# Ponte_H.net
KiCad netlist of a schematic drawn in Altium Designer
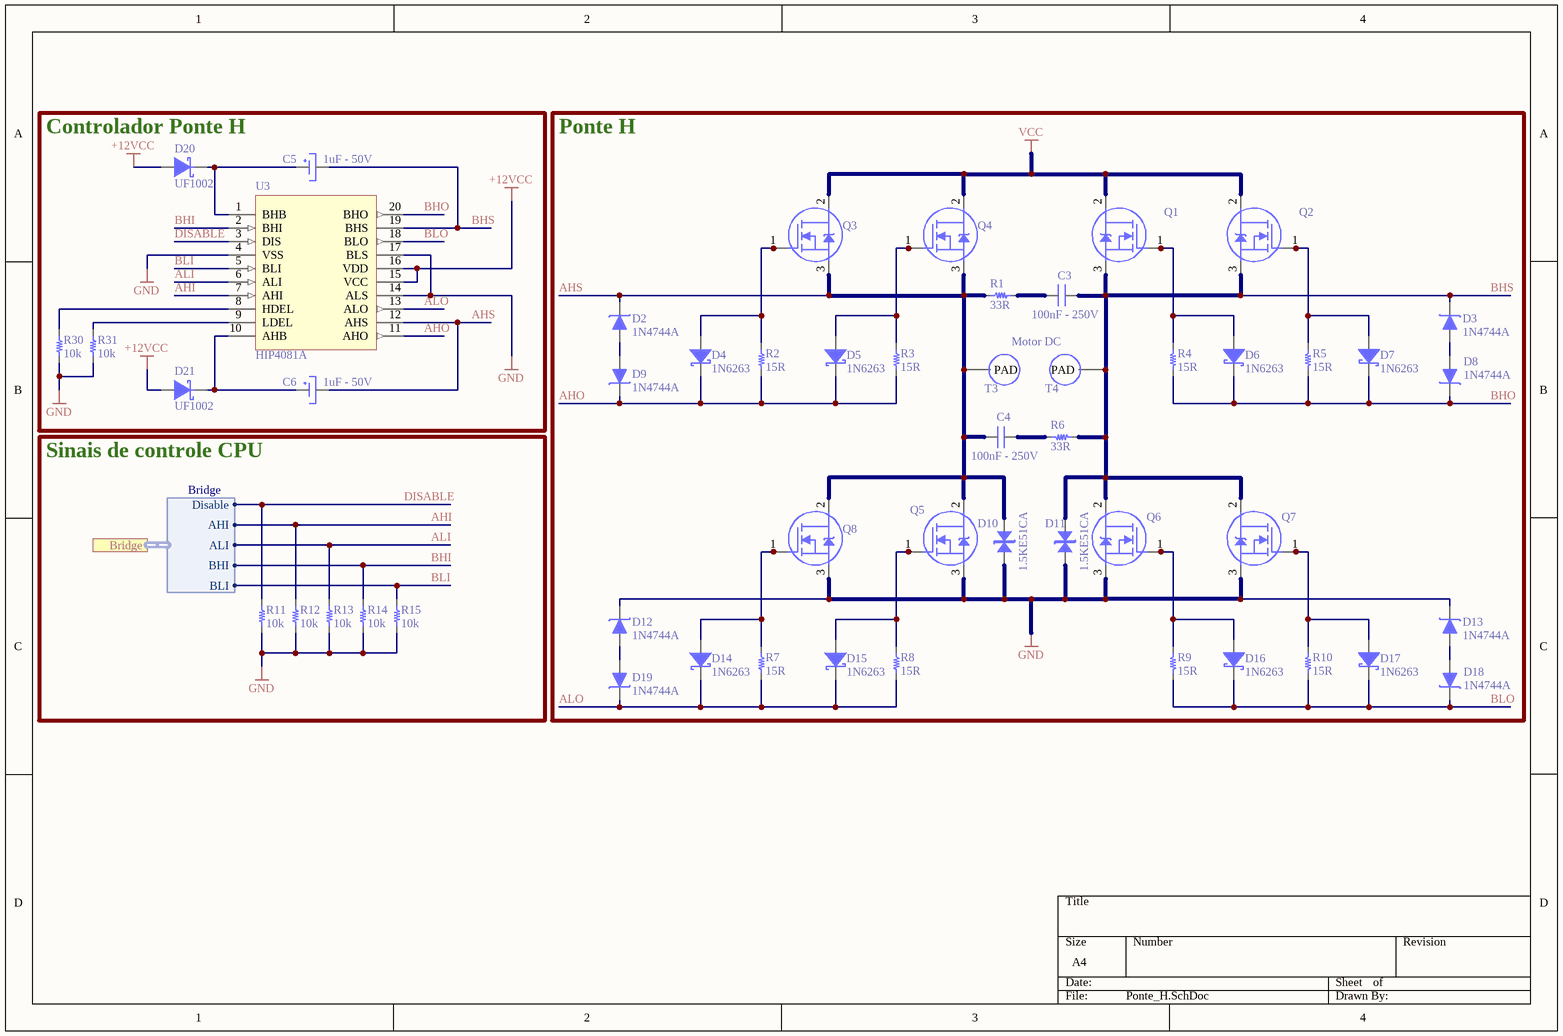
[diagram p0: Ponte_H.SchDoc]

(export (version "E")
  (design (tool "Eeschema 10.0.6"))
  (components
    (comp (ref "C3")
      (value "100nF - 250V")
      (footprint "Capacitor_PTH")
      (description "Capacitor_100nF Poliester")
      (libsource (lib "bike") (part "100nF - 250V"))
    )
    (comp (ref "C4")
      (value "100nF - 250V")
      (footprint "Capacitor_PTH")
      (description "Capacitor_100nF Poliester")
      (libsource (lib "bike") (part "100nF - 250V"))
    )
    (comp (ref "C5")
      (value "1uF - 50V")
      (footprint "CAPACITOR_SMD")
      (description "Capacitor_1uF_50V")
      (libsource (lib "bike") (part "1uF - 50V"))
    )
    (comp (ref "C6")
      (value "1uF - 50V")
      (footprint "CAPACITOR_SMD")
      (description "Capacitor_1uF_50V")
      (libsource (lib "bike") (part "1uF - 50V"))
    )
    (comp (ref "D2")
      (value "1N4744A")
      (footprint "Diode_PHT")
      (description "Diodo Zener 15V 200mA")
      (libsource (lib "bike") (part "1N4744A"))
    )
    (comp (ref "D3")
      (value "1N4744A")
      (footprint "Diode_PHT")
      (description "Diodo Zener 15V 200mA")
      (libsource (lib "bike") (part "1N4744A"))
    )
    (comp (ref "D4")
      (value "1N6263")
      (footprint "Diode_PHT")
      (description "Diodo Schottky 60V - 15mA")
      (libsource (lib "bike") (part "1N6263"))
    )
    (comp (ref "D5")
      (value "1N6263")
      (footprint "Diode_PHT")
      (description "Diodo Schottky 60V - 15mA")
      (libsource (lib "bike") (part "1N6263"))
    )
    (comp (ref "D6")
      (value "1N6263")
      (footprint "Diode_PHT")
      (description "Diodo Schottky 60V - 15mA")
      (libsource (lib "bike") (part "1N6263"))
    )
    (comp (ref "D7")
      (value "1N6263")
      (footprint "Diode_PHT")
      (description "Diodo Schottky 60V - 15mA")
      (libsource (lib "bike") (part "1N6263"))
    )
    (comp (ref "D8")
      (value "1N4744A")
      (footprint "Diode_PHT")
      (description "Diodo Zener 15V 200mA")
      (libsource (lib "bike") (part "1N4744A"))
    )
    (comp (ref "D9")
      (value "1N4744A")
      (footprint "Diode_PHT")
      (description "Diodo Zener 15V 200mA")
      (libsource (lib "bike") (part "1N4744A"))
    )
    (comp (ref "D10")
      (value "1.5KE51CA")
      (footprint "DO-201")
      (description "Transzorb")
      (libsource (lib "bike") (part "1.5KE51CA"))
    )
    (comp (ref "D11")
      (value "1.5KE51CA")
      (footprint "DO-201")
      (description "Transzorb")
      (libsource (lib "bike") (part "1.5KE51CA"))
    )
    (comp (ref "D12")
      (value "1N4744A")
      (footprint "Diode_PHT")
      (description "Diodo Zener 15V 200mA")
      (libsource (lib "bike") (part "1N4744A"))
    )
    (comp (ref "D13")
      (value "1N4744A")
      (footprint "Diode_PHT")
      (description "Diodo Zener 15V 200mA")
      (libsource (lib "bike") (part "1N4744A"))
    )
    (comp (ref "D14")
      (value "1N6263")
      (footprint "Diode_PHT")
      (description "Diodo Schottky 60V - 15mA")
      (libsource (lib "bike") (part "1N6263"))
    )
    (comp (ref "D15")
      (value "1N6263")
      (footprint "Diode_PHT")
      (description "Diodo Schottky 60V - 15mA")
      (libsource (lib "bike") (part "1N6263"))
    )
    (comp (ref "D16")
      (value "1N6263")
      (footprint "Diode_PHT")
      (description "Diodo Schottky 60V - 15mA")
      (libsource (lib "bike") (part "1N6263"))
    )
    (comp (ref "D17")
      (value "1N6263")
      (footprint "Diode_PHT")
      (description "Diodo Schottky 60V - 15mA")
      (libsource (lib "bike") (part "1N6263"))
    )
    (comp (ref "D18")
      (value "1N4744A")
      (footprint "Diode_PHT")
      (description "Diodo Zener 15V 200mA")
      (libsource (lib "bike") (part "1N4744A"))
    )
    (comp (ref "D19")
      (value "1N4744A")
      (footprint "Diode_PHT")
      (description "Diodo Zener 15V 200mA")
      (libsource (lib "bike") (part "1N4744A"))
    )
    (comp (ref "D20")
      (value "UF1002")
      (footprint "Diode_PHT")
      (description "UltraFast Diode 1.0A")
      (libsource (lib "bike") (part "UF1002"))
    )
    (comp (ref "D21")
      (value "UF1002")
      (footprint "Diode_PHT")
      (description "UltraFast Diode 1.0A")
      (libsource (lib "bike") (part "UF1002"))
    )
    (comp (ref "Q1")
      (value "IRF1405")
      (footprint "TO-220AB")
      (description "MOSFET transistor")
      (libsource (lib "bike") (part "IRF1405"))
    )
    (comp (ref "Q2")
      (value "IRF1405")
      (footprint "TO-220AB")
      (description "MOSFET transistor")
      (libsource (lib "bike") (part "IRF1405"))
    )
    (comp (ref "Q3")
      (value "IRF1405")
      (footprint "TO-220AB")
      (description "MOSFET transistor")
      (libsource (lib "") (part "IRF1405_1"))
    )
    (comp (ref "Q4")
      (value "IRF1405")
      (footprint "TO-220AB")
      (description "MOSFET transistor")
      (libsource (lib "") (part "IRF1405_1"))
    )
    (comp (ref "Q5")
      (value "IRF1405")
      (footprint "TO-220AB")
      (description "MOSFET transistor")
      (libsource (lib "") (part "IRF1405_1"))
    )
    (comp (ref "Q6")
      (value "IRF1405")
      (footprint "TO-220AB")
      (description "MOSFET transistor")
      (libsource (lib "bike") (part "IRF1405"))
    )
    (comp (ref "Q7")
      (value "IRF1405")
      (footprint "TO-220AB")
      (description "MOSFET transistor")
      (libsource (lib "bike") (part "IRF1405"))
    )
    (comp (ref "Q8")
      (value "IRF1405")
      (footprint "TO-220AB")
      (description "MOSFET transistor")
      (libsource (lib "") (part "IRF1405_1"))
    )
    (comp (ref "R1")
      (value "33R")
      (footprint "Resistor_PTH")
      (description "Resistor PHT")
      (libsource (lib "bike") (part "Resistor_33R"))
    )
    (comp (ref "R2")
      (value "15R")
      (footprint "R_0805")
      (description "Resistor padrão 0805")
      (libsource (lib "bike") (part "Resistor_15R"))
    )
    (comp (ref "R3")
      (value "15R")
      (footprint "R_0805")
      (description "Resistor padrão 0805")
      (libsource (lib "bike") (part "Resistor_15R"))
    )
    (comp (ref "R4")
      (value "15R")
      (footprint "R_0805")
      (description "Resistor padrão 0805")
      (libsource (lib "bike") (part "Resistor_15R"))
    )
    (comp (ref "R5")
      (value "15R")
      (footprint "R_0805")
      (description "Resistor padrão 0805")
      (libsource (lib "bike") (part "Resistor_15R"))
    )
    (comp (ref "R6")
      (value "33R")
      (footprint "Resistor_PTH")
      (description "Resistor PHT")
      (libsource (lib "bike") (part "Resistor_33R"))
    )
    (comp (ref "R7")
      (value "15R")
      (footprint "R_0805")
      (description "Resistor padrão 0805")
      (libsource (lib "bike") (part "Resistor_15R"))
    )
    (comp (ref "R8")
      (value "15R")
      (footprint "R_0805")
      (description "Resistor padrão 0805")
      (libsource (lib "bike") (part "Resistor_15R"))
    )
    (comp (ref "R9")
      (value "15R")
      (footprint "R_0805")
      (description "Resistor padrão 0805")
      (libsource (lib "bike") (part "Resistor_15R"))
    )
    (comp (ref "R10")
      (value "15R")
      (footprint "R_0805")
      (description "Resistor padrão 0805")
      (libsource (lib "bike") (part "Resistor_15R"))
    )
    (comp (ref "R11")
      (value "10k")
      (footprint "R_0805")
      (description "Resistor padrão 0805")
      (libsource (lib "bike") (part "Resistor_10K"))
    )
    (comp (ref "R12")
      (value "10k")
      (footprint "R_0805")
      (description "Resistor padrão 0805")
      (libsource (lib "bike") (part "Resistor_10K"))
    )
    (comp (ref "R13")
      (value "10k")
      (footprint "R_0805")
      (description "Resistor padrão 0805")
      (libsource (lib "bike") (part "Resistor_10K"))
    )
    (comp (ref "R14")
      (value "10k")
      (footprint "R_0805")
      (description "Resistor padrão 0805")
      (libsource (lib "bike") (part "Resistor_10K"))
    )
    (comp (ref "R15")
      (value "10k")
      (footprint "R_0805")
      (description "Resistor padrão 0805")
      (libsource (lib "bike") (part "Resistor_10K"))
    )
    (comp (ref "R30")
      (value "10k")
      (footprint "R_0805")
      (description "Resistor padrão 0805")
      (libsource (lib "bike") (part "Resistor_10K"))
    )
    (comp (ref "R31")
      (value "10k")
      (footprint "R_0805")
      (description "Resistor padrão 0805")
      (libsource (lib "bike") (part "Resistor_10K"))
    )
    (comp (ref "T3")
      (value "Power_Pad")
      (footprint "Power_Pad")
      (description "Terminal de alta potência para soldar os cabos de potência")
      (libsource (lib "bike") (part "Power_Pad"))
    )
    (comp (ref "T4")
      (value "Power_Pad")
      (footprint "Power_Pad")
      (description "Terminal de alta potência para soldar os cabos de potência")
      (libsource (lib "bike") (part "Power_Pad"))
    )
    (comp (ref "U3")
      (value "HIP4081A")
      (footprint "PDIP20")
      (description "High Frequency Full Bridge FET Driver")
      (libsource (lib "bike") (part "HIP4081A"))
    )
  )
  (nets
    (net (code "2") (name "+12VCC") (class "Default")
      (node (ref "D20") (pin "A") (pinfunction "Anodo_A") (pintype "passive"))
      (node (ref "D21") (pin "A") (pinfunction "Anodo_A") (pintype "passive"))
      (node (ref "U3") (pin "15") (pinfunction "VCC_15") (pintype "power_in"))
      (node (ref "U3") (pin "16") (pinfunction "VDD_16") (pintype "power_in"))
    )
    (net (code "3") (name "/AHI") (class "Default")
      (node (ref "R12") (pin "2") (pinfunction "2_2") (pintype "passive"))
      (node (ref "U3") (pin "7") (pinfunction "AHI_7") (pintype "input"))
    )
    (net (code "4") (name "/AHO") (class "Default")
      (node (ref "D4") (pin "K") (pinfunction "Catodo_K") (pintype "passive"))
      (node (ref "D5") (pin "K") (pinfunction "Catodo_K") (pintype "passive"))
      (node (ref "D9") (pin "K") (pinfunction "Catodo_K") (pintype "passive"))
      (node (ref "R2") (pin "1") (pinfunction "1_1") (pintype "passive"))
      (node (ref "R3") (pin "1") (pinfunction "1_1") (pintype "passive"))
      (node (ref "U3") (pin "11") (pinfunction "AHO_11") (pintype "output"))
    )
    (net (code "5") (name "/AHS") (class "Default")
      (node (ref "C4") (pin "1") (pinfunction "1_1") (pintype "passive"))
      (node (ref "C6") (pin "1") (pinfunction "1_1") (pintype "passive"))
      (node (ref "D10") (pin "K") (pinfunction "Catodo_K") (pintype "passive"))
      (node (ref "D2") (pin "K") (pinfunction "Catodo_K") (pintype "passive"))
      (node (ref "Q3") (pin "3") (pinfunction "Source_3") (pintype "power_in"))
      (node (ref "Q4") (pin "3") (pinfunction "Source_3") (pintype "power_in"))
      (node (ref "Q5") (pin "2") (pinfunction "Drain_2") (pintype "power_in"))
      (node (ref "Q8") (pin "2") (pinfunction "Drain_2") (pintype "power_in"))
      (node (ref "R1") (pin "1") (pinfunction "1_1") (pintype "passive"))
      (node (ref "T3") (pin "1") (pinfunction "PAD_1") (pintype "power_in"))
      (node (ref "U3") (pin "12") (pinfunction "AHS_12") (pintype "power_in"))
    )
    (net (code "6") (name "/ALI") (class "Default")
      (node (ref "R13") (pin "2") (pinfunction "2_2") (pintype "passive"))
      (node (ref "U3") (pin "6") (pinfunction "ALI_6") (pintype "input"))
    )
    (net (code "7") (name "/ALO") (class "Default")
      (node (ref "D14") (pin "K") (pinfunction "Catodo_K") (pintype "passive"))
      (node (ref "D15") (pin "K") (pinfunction "Catodo_K") (pintype "passive"))
      (node (ref "D19") (pin "K") (pinfunction "Catodo_K") (pintype "passive"))
      (node (ref "R7") (pin "1") (pinfunction "1_1") (pintype "passive"))
      (node (ref "R8") (pin "1") (pinfunction "1_1") (pintype "passive"))
      (node (ref "U3") (pin "13") (pinfunction "ALO_13") (pintype "output"))
    )
    (net (code "8") (name "/BHI") (class "Default")
      (node (ref "R14") (pin "2") (pinfunction "2_2") (pintype "passive"))
      (node (ref "U3") (pin "2") (pinfunction "BHI_2") (pintype "input"))
    )
    (net (code "9") (name "/BHO") (class "Default")
      (node (ref "D6") (pin "K") (pinfunction "Catodo_K") (pintype "passive"))
      (node (ref "D7") (pin "K") (pinfunction "Catodo_K") (pintype "passive"))
      (node (ref "D8") (pin "K") (pinfunction "Catodo_K") (pintype "passive"))
      (node (ref "R4") (pin "1") (pinfunction "1_1") (pintype "passive"))
      (node (ref "R5") (pin "1") (pinfunction "1_1") (pintype "passive"))
      (node (ref "U3") (pin "20") (pinfunction "BHO_20") (pintype "output"))
    )
    (net (code "10") (name "/BHS") (class "Default")
      (node (ref "C3") (pin "1") (pinfunction "1_1") (pintype "passive"))
      (node (ref "C5") (pin "1") (pinfunction "1_1") (pintype "passive"))
      (node (ref "D11") (pin "K") (pinfunction "Catodo_K") (pintype "passive"))
      (node (ref "D3") (pin "K") (pinfunction "Catodo_K") (pintype "passive"))
      (node (ref "Q1") (pin "3") (pinfunction "Source_3") (pintype "power_in"))
      (node (ref "Q2") (pin "3") (pinfunction "Source_3") (pintype "power_in"))
      (node (ref "Q6") (pin "2") (pinfunction "Drain_2") (pintype "power_in"))
      (node (ref "Q7") (pin "2") (pinfunction "Drain_2") (pintype "power_in"))
      (node (ref "R6") (pin "1") (pinfunction "1_1") (pintype "passive"))
      (node (ref "T4") (pin "1") (pinfunction "PAD_1") (pintype "power_in"))
      (node (ref "U3") (pin "19") (pinfunction "BHS_19") (pintype "power_in"))
    )
    (net (code "11") (name "/BLI") (class "Default")
      (node (ref "R15") (pin "2") (pinfunction "2_2") (pintype "passive"))
      (node (ref "U3") (pin "5") (pinfunction "BLI_5") (pintype "input"))
    )
    (net (code "12") (name "/BLO") (class "Default")
      (node (ref "D16") (pin "K") (pinfunction "Catodo_K") (pintype "passive"))
      (node (ref "D17") (pin "K") (pinfunction "Catodo_K") (pintype "passive"))
      (node (ref "D18") (pin "K") (pinfunction "Catodo_K") (pintype "passive"))
      (node (ref "R10") (pin "1") (pinfunction "1_1") (pintype "passive"))
      (node (ref "R9") (pin "1") (pinfunction "1_1") (pintype "passive"))
      (node (ref "U3") (pin "18") (pinfunction "BLO_18") (pintype "output"))
    )
    (net (code "13") (name "/DISABLE") (class "Default")
      (node (ref "R11") (pin "2") (pinfunction "2_2") (pintype "passive"))
      (node (ref "U3") (pin "3") (pinfunction "DIS_3") (pintype "input"))
    )
    (net (code "15") (name "GND") (class "Default")
      (node (ref "D10") (pin "A") (pinfunction "Anodo_A") (pintype "passive"))
      (node (ref "D11") (pin "A") (pinfunction "Anodo_A") (pintype "passive"))
      (node (ref "D12") (pin "K") (pinfunction "Catodo_K") (pintype "passive"))
      (node (ref "D13") (pin "K") (pinfunction "Catodo_K") (pintype "passive"))
      (node (ref "Q5") (pin "3") (pinfunction "Source_3") (pintype "power_in"))
      (node (ref "Q6") (pin "3") (pinfunction "Source_3") (pintype "power_in"))
      (node (ref "Q7") (pin "3") (pinfunction "Source_3") (pintype "power_in"))
      (node (ref "Q8") (pin "3") (pinfunction "Source_3") (pintype "power_in"))
      (node (ref "R11") (pin "1") (pinfunction "1_1") (pintype "passive"))
      (node (ref "R12") (pin "1") (pinfunction "1_1") (pintype "passive"))
      (node (ref "R13") (pin "1") (pinfunction "1_1") (pintype "passive"))
      (node (ref "R14") (pin "1") (pinfunction "1_1") (pintype "passive"))
      (node (ref "R15") (pin "1") (pinfunction "1_1") (pintype "passive"))
      (node (ref "R30") (pin "1") (pinfunction "1_1") (pintype "passive"))
      (node (ref "R31") (pin "1") (pinfunction "1_1") (pintype "passive"))
      (node (ref "U3") (pin "14") (pinfunction "ALS_14") (pintype "power_in"))
      (node (ref "U3") (pin "17") (pinfunction "BLS_17") (pintype "power_in"))
      (node (ref "U3") (pin "4") (pinfunction "VSS_4") (pintype "power_in"))
    )
    (net (code "16") (name "Net-(C3-Pad2)") (class "Default")
      (node (ref "C3") (pin "2") (pinfunction "2_2") (pintype "passive"))
      (node (ref "R1") (pin "2") (pinfunction "2_2") (pintype "passive"))
    )
    (net (code "17") (name "Net-(C4-Pad2)") (class "Default")
      (node (ref "C4") (pin "2") (pinfunction "2_2") (pintype "passive"))
      (node (ref "R6") (pin "2") (pinfunction "2_2") (pintype "passive"))
    )
    (net (code "18") (name "Net-(D2-Anodo)") (class "Default")
      (node (ref "D2") (pin "A") (pinfunction "Anodo_A") (pintype "passive"))
      (node (ref "D9") (pin "A") (pinfunction "Anodo_A") (pintype "passive"))
    )
    (net (code "19") (name "Net-(D3-Anodo)") (class "Default")
      (node (ref "D3") (pin "A") (pinfunction "Anodo_A") (pintype "passive"))
      (node (ref "D8") (pin "A") (pinfunction "Anodo_A") (pintype "passive"))
    )
    (net (code "20") (name "Net-(D4-Anodo)") (class "Default")
      (node (ref "D4") (pin "A") (pinfunction "Anodo_A") (pintype "passive"))
      (node (ref "Q3") (pin "1") (pinfunction "Gate_1") (pintype "power_in"))
      (node (ref "R2") (pin "2") (pinfunction "2_2") (pintype "passive"))
    )
    (net (code "21") (name "Net-(D5-Anodo)") (class "Default")
      (node (ref "D5") (pin "A") (pinfunction "Anodo_A") (pintype "passive"))
      (node (ref "Q4") (pin "1") (pinfunction "Gate_1") (pintype "power_in"))
      (node (ref "R3") (pin "2") (pinfunction "2_2") (pintype "passive"))
    )
    (net (code "22") (name "Net-(D6-Anodo)") (class "Default")
      (node (ref "D6") (pin "A") (pinfunction "Anodo_A") (pintype "passive"))
      (node (ref "Q1") (pin "1") (pinfunction "Gate_1") (pintype "power_in"))
      (node (ref "R4") (pin "2") (pinfunction "2_2") (pintype "passive"))
    )
    (net (code "23") (name "Net-(D7-Anodo)") (class "Default")
      (node (ref "D7") (pin "A") (pinfunction "Anodo_A") (pintype "passive"))
      (node (ref "Q2") (pin "1") (pinfunction "Gate_1") (pintype "power_in"))
      (node (ref "R5") (pin "2") (pinfunction "2_2") (pintype "passive"))
    )
    (net (code "24") (name "Net-(D12-Anodo)") (class "Default")
      (node (ref "D12") (pin "A") (pinfunction "Anodo_A") (pintype "passive"))
      (node (ref "D19") (pin "A") (pinfunction "Anodo_A") (pintype "passive"))
    )
    (net (code "25") (name "Net-(D13-Anodo)") (class "Default")
      (node (ref "D13") (pin "A") (pinfunction "Anodo_A") (pintype "passive"))
      (node (ref "D18") (pin "A") (pinfunction "Anodo_A") (pintype "passive"))
    )
    (net (code "26") (name "Net-(D14-Anodo)") (class "Default")
      (node (ref "D14") (pin "A") (pinfunction "Anodo_A") (pintype "passive"))
      (node (ref "Q8") (pin "1") (pinfunction "Gate_1") (pintype "power_in"))
      (node (ref "R7") (pin "2") (pinfunction "2_2") (pintype "passive"))
    )
    (net (code "27") (name "Net-(D15-Anodo)") (class "Default")
      (node (ref "D15") (pin "A") (pinfunction "Anodo_A") (pintype "passive"))
      (node (ref "Q5") (pin "1") (pinfunction "Gate_1") (pintype "power_in"))
      (node (ref "R8") (pin "2") (pinfunction "2_2") (pintype "passive"))
    )
    (net (code "28") (name "Net-(D16-Anodo)") (class "Default")
      (node (ref "D16") (pin "A") (pinfunction "Anodo_A") (pintype "passive"))
      (node (ref "Q6") (pin "1") (pinfunction "Gate_1") (pintype "power_in"))
      (node (ref "R9") (pin "2") (pinfunction "2_2") (pintype "passive"))
    )
    (net (code "29") (name "Net-(D17-Anodo)") (class "Default")
      (node (ref "D17") (pin "A") (pinfunction "Anodo_A") (pintype "passive"))
      (node (ref "Q7") (pin "1") (pinfunction "Gate_1") (pintype "power_in"))
      (node (ref "R10") (pin "2") (pinfunction "2_2") (pintype "passive"))
    )
    (net (code "30") (name "Net-(D20-Catodo)") (class "Default")
      (node (ref "C5") (pin "2") (pinfunction "2_2") (pintype "passive"))
      (node (ref "D20") (pin "K") (pinfunction "Catodo_K") (pintype "passive"))
      (node (ref "U3") (pin "1") (pinfunction "BHB_1") (pintype "power_in"))
    )
    (net (code "31") (name "Net-(D21-Catodo)") (class "Default")
      (node (ref "C6") (pin "2") (pinfunction "2_2") (pintype "passive"))
      (node (ref "D21") (pin "K") (pinfunction "Catodo_K") (pintype "passive"))
      (node (ref "U3") (pin "10") (pinfunction "AHB_10") (pintype "power_in"))
    )
    (net (code "32") (name "Net-(U3-HDEL)") (class "Default")
      (node (ref "R30") (pin "2") (pinfunction "2_2") (pintype "passive"))
      (node (ref "U3") (pin "8") (pinfunction "HDEL_8") (pintype "passive"))
    )
    (net (code "33") (name "Net-(U3-LDEL)") (class "Default")
      (node (ref "R31") (pin "2") (pinfunction "2_2") (pintype "passive"))
      (node (ref "U3") (pin "9") (pinfunction "LDEL_9") (pintype "passive"))
    )
    (net (code "34") (name "VCC") (class "Default")
      (node (ref "Q1") (pin "2") (pinfunction "Drain_2") (pintype "power_in"))
      (node (ref "Q2") (pin "2") (pinfunction "Drain_2") (pintype "power_in"))
      (node (ref "Q3") (pin "2") (pinfunction "Drain_2") (pintype "power_in"))
      (node (ref "Q4") (pin "2") (pinfunction "Drain_2") (pintype "power_in"))
    )
  )
)
